# whte_noise.net
KiCad netlist of a schematic drawn in Altium Designer
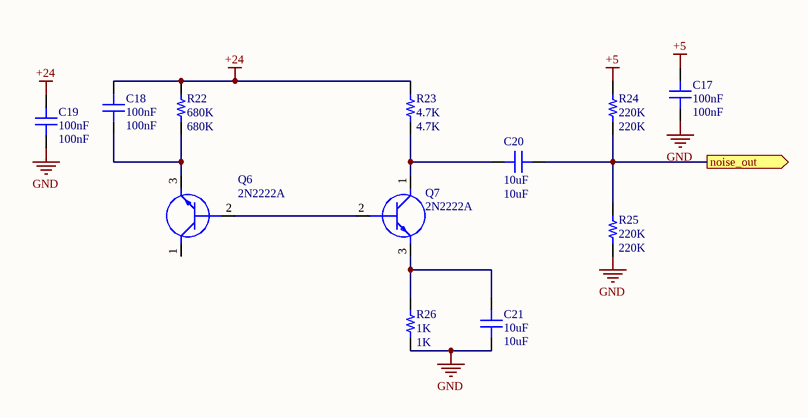
[diagram p0: whte_noise.SchDoc]

(export (version "E")
  (design (tool "Eeschema 10.0.6"))
  (components
    (comp (ref "C17")
      (value "100nF")
      (footprint "cap805")
      (description "CAP SMD 0805")
      (fields (field (name "PART NUMBER") "C0805X106K9RAC7800") (field (name "ALTIUM_VALUE") "100nF"))
      (libsource (lib "lamp control-ver2") (part "Capacitor"))
    )
    (comp (ref "C18")
      (value "100nF")
      (footprint "cap805")
      (description "CAP SMD 0805")
      (fields (field (name "PART NUMBER") "C0805X106K9RAC7800") (field (name "ALTIUM_VALUE") "100nF"))
      (libsource (lib "lamp control-ver2") (part "Capacitor"))
    )
    (comp (ref "C19")
      (value "100nF")
      (footprint "cap805")
      (description "CAP SMD 0805")
      (fields (field (name "PART NUMBER") "C0805X106K9RAC7800") (field (name "ALTIUM_VALUE") "100nF"))
      (libsource (lib "lamp control-ver2") (part "Capacitor"))
    )
    (comp (ref "C20")
      (value "10uF")
      (footprint "cap805")
      (description "CAP SMD 0805")
      (fields (field (name "PART NUMBER") "C0805X106K9RAC7800") (field (name "ALTIUM_VALUE") "10uF"))
      (libsource (lib "lamp control-ver2") (part "Capacitor"))
    )
    (comp (ref "C21")
      (value "10uF")
      (footprint "cap805")
      (description "CAP SMD 0805")
      (fields (field (name "PART NUMBER") "C0805X106K9RAC7800") (field (name "ALTIUM_VALUE") "10uF"))
      (libsource (lib "lamp control-ver2") (part "Capacitor"))
    )
    (comp (ref "Q6")
      (value "2N2222A")
      (footprint "soT95p280x130-3n")
      (description "Transistor BJT NPN SMD")
      (libsource (lib "*") (part "2N2222A"))
    )
    (comp (ref "Q7")
      (value "2N2222A")
      (footprint "soT95p280x130-3n")
      (description "Transistor BJT NPN SMD")
      (libsource (lib "*") (part "2N2222A"))
    )
    (comp (ref "R22")
      (value "680K")
      (footprint "0603R")
      (description "RES SMD 0603")
      (fields (field (name "PART NUMBER") "RCS0805100KFKEA") (field (name "ALTIUM_VALUE") "680K"))
      (libsource (lib "lamp control-ver2") (part "Resistor"))
    )
    (comp (ref "R23")
      (value "4.7K")
      (footprint "0603R")
      (description "RES SMD 0603")
      (fields (field (name "PART NUMBER") "RCS0805100KFKEA") (field (name "ALTIUM_VALUE") "4.7K"))
      (libsource (lib "lamp control-ver2") (part "Resistor"))
    )
    (comp (ref "R24")
      (value "220K")
      (footprint "0603R")
      (description "RES SMD 0603")
      (fields (field (name "PART NUMBER") "RCS0805100KFKEA") (field (name "ALTIUM_VALUE") "220K"))
      (libsource (lib "lamp control-ver2") (part "Resistor"))
    )
    (comp (ref "R25")
      (value "220K")
      (footprint "0603R")
      (description "RES SMD 0603")
      (fields (field (name "PART NUMBER") "RCS0805100KFKEA") (field (name "ALTIUM_VALUE") "220K"))
      (libsource (lib "lamp control-ver2") (part "Resistor"))
    )
    (comp (ref "R26")
      (value "1K")
      (footprint "0603R")
      (description "RES SMD 0603")
      (fields (field (name "PART NUMBER") "RCS0805100KFKEA") (field (name "ALTIUM_VALUE") "1K"))
      (libsource (lib "lamp control-ver2") (part "Resistor"))
    )
  )
  (nets
    (net (code "1") (name "+5") (class "Default")
      (node (ref "C17") (pin "1") (pinfunction "1_1") (pintype "passive"))
      (node (ref "R24") (pin "2") (pinfunction "2_2") (pintype "passive"))
    )
    (net (code "2") (name "+24") (class "Default")
      (node (ref "C18") (pin "2") (pinfunction "2_2") (pintype "passive"))
      (node (ref "C19") (pin "1") (pinfunction "1_1") (pintype "passive"))
      (node (ref "R22") (pin "2") (pinfunction "2_2") (pintype "passive"))
      (node (ref "R23") (pin "2") (pinfunction "2_2") (pintype "passive"))
    )
    (net (code "3") (name "/noise_out") (class "Default")
      (node (ref "C20") (pin "1") (pinfunction "1_1") (pintype "passive"))
      (node (ref "R24") (pin "1") (pinfunction "1_1") (pintype "passive"))
      (node (ref "R25") (pin "2") (pinfunction "2_2") (pintype "passive"))
    )
    (net (code "4") (name "GND") (class "Default")
      (node (ref "C17") (pin "2") (pinfunction "2_2") (pintype "passive"))
      (node (ref "C19") (pin "2") (pinfunction "2_2") (pintype "passive"))
      (node (ref "C21") (pin "1") (pinfunction "1_1") (pintype "passive"))
      (node (ref "R25") (pin "1") (pinfunction "1_1") (pintype "passive"))
      (node (ref "R26") (pin "1") (pinfunction "1_1") (pintype "passive"))
    )
    (net (code "5") (name "Net-(Q6-B)") (class "Default")
      (node (ref "Q6") (pin "2") (pinfunction "B_2") (pintype "passive"))
      (node (ref "Q7") (pin "2") (pinfunction "B_2") (pintype "passive"))
    )
    (net (code "6") (name "Net-(Q6-E)") (class "Default")
      (node (ref "C18") (pin "1") (pinfunction "1_1") (pintype "passive"))
      (node (ref "Q6") (pin "3") (pinfunction "E_3") (pintype "passive"))
      (node (ref "R22") (pin "1") (pinfunction "1_1") (pintype "passive"))
    )
    (net (code "7") (name "Net-(Q7-C)") (class "Default")
      (node (ref "C20") (pin "2") (pinfunction "2_2") (pintype "passive"))
      (node (ref "Q7") (pin "1") (pinfunction "C_1") (pintype "passive"))
      (node (ref "R23") (pin "1") (pinfunction "1_1") (pintype "passive"))
    )
    (net (code "8") (name "Net-(Q7-E)") (class "Default")
      (node (ref "C21") (pin "2") (pinfunction "2_2") (pintype "passive"))
      (node (ref "Q7") (pin "3") (pinfunction "E_3") (pintype "passive"))
      (node (ref "R26") (pin "2") (pinfunction "2_2") (pintype "passive"))
    )
    (net (code "9") (name "unconnected-(Q6-C-Pad1)") (class "Default")
      (node (ref "Q6") (pin "1") (pinfunction "C_1") (pintype "passive"))
    )
  )
)
